# bqZUM_USB.net
KiCad netlist of a schematic drawn in Altium Designer
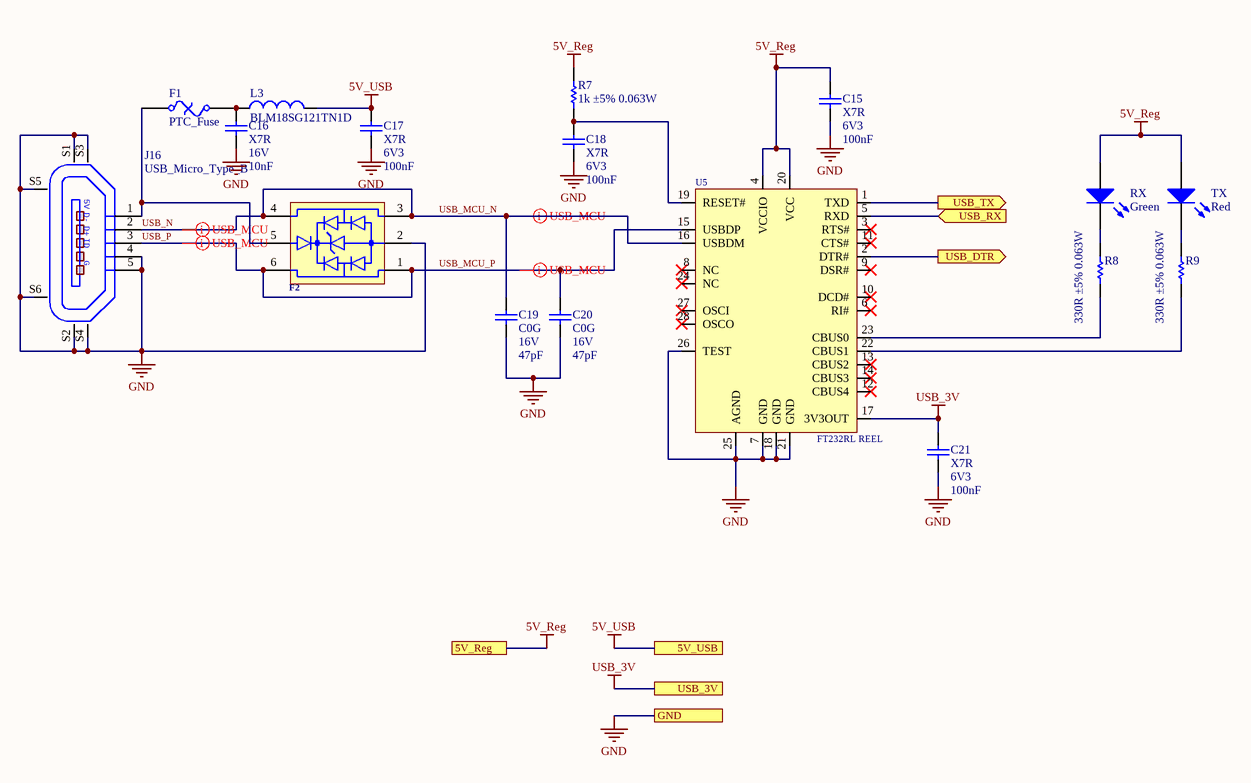
[diagram p0: bqZUM_USB.SchDoc]

(export (version "E")
  (design (tool "Eeschema 10.0.6"))
  (components
    (comp (ref "C15")
      (value "Capacitor")
      (footprint "C0402")
      (fields
        (field (name "DIELECTRIC") "X7R")
        (field (name "VOLTAGE") "6V3")
        (field (name "CAPACITANCE") "100nF")
        (field (name "PART NUMBER") "C0402_100nF_6V3_±10%")
        (field (name "TOLERANCE") "±10%")
        (field (name "MANUFACTURER") "Kemet")
      )
      (libsource (lib "Pasives_Capacitor_SMD") (part "Capacitor"))
    )
    (comp (ref "C16")
      (value "Capacitor")
      (footprint "C0402")
      (fields
        (field (name "DIELECTRIC") "X7R")
        (field (name "VOLTAGE") "16V")
        (field (name "CAPACITANCE") "10nF")
        (field (name "PART NUMBER") "C0402_10nF_16V_±10%")
        (field (name "TOLERANCE") "±10%")
        (field (name "MANUFACTURER") "Kemet")
      )
      (libsource (lib "Pasives_Capacitor_SMD") (part "Capacitor"))
    )
    (comp (ref "C17")
      (value "Capacitor")
      (footprint "C0402")
      (fields
        (field (name "DIELECTRIC") "X7R")
        (field (name "VOLTAGE") "6V3")
        (field (name "CAPACITANCE") "100nF")
        (field (name "PART NUMBER") "C0402_100nF_6V3_±10%")
        (field (name "TOLERANCE") "±10%")
        (field (name "MANUFACTURER") "Kemet")
      )
      (libsource (lib "Pasives_Capacitor_SMD") (part "Capacitor"))
    )
    (comp (ref "C18")
      (value "Capacitor")
      (footprint "C0402")
      (fields
        (field (name "DIELECTRIC") "X7R")
        (field (name "VOLTAGE") "6V3")
        (field (name "CAPACITANCE") "100nF")
        (field (name "PART NUMBER") "C0402_100nF_6V3_±10%")
        (field (name "TOLERANCE") "±10%")
        (field (name "MANUFACTURER") "Kemet")
      )
      (libsource (lib "Pasives_Capacitor_SMD") (part "Capacitor"))
    )
    (comp (ref "C19")
      (value "Capacitor")
      (footprint "C0402")
      (fields
        (field (name "DIELECTRIC") "C0G")
        (field (name "VOLTAGE") "16V")
        (field (name "CAPACITANCE") "47pF")
        (field (name "PART NUMBER") "C0402_47pF_16V_±10%")
        (field (name "TOLERANCE") "±10%")
        (field (name "MANUFACTURER") "Kemet")
      )
      (libsource (lib "Pasives_Capacitor_SMD") (part "Capacitor"))
    )
    (comp (ref "C20")
      (value "Capacitor")
      (footprint "C0402")
      (fields
        (field (name "DIELECTRIC") "C0G")
        (field (name "VOLTAGE") "16V")
        (field (name "CAPACITANCE") "47pF")
        (field (name "PART NUMBER") "C0402_47pF_16V_±10%")
        (field (name "TOLERANCE") "±10%")
        (field (name "MANUFACTURER") "Kemet")
      )
      (libsource (lib "Pasives_Capacitor_SMD") (part "Capacitor"))
    )
    (comp (ref "C21")
      (value "Capacitor")
      (footprint "C0402")
      (fields
        (field (name "DIELECTRIC") "X7R")
        (field (name "VOLTAGE") "6V3")
        (field (name "CAPACITANCE") "100nF")
        (field (name "PART NUMBER") "C0402_100nF_6V3_±10%")
        (field (name "TOLERANCE") "±10%")
        (field (name "MANUFACTURER") "Kemet")
      )
      (libsource (lib "Pasives_Capacitor_SMD") (part "Capacitor"))
    )
    (comp (ref "F1")
      (value "PTC_Fuse")
      (footprint "F1812")
      (description "PTC Resettable Fuse")
      (fields (field (name "PART NUMBER") "FUSE 0.5A 15V") (field (name "VOLTAGE") "15V"))
      (libsource (lib "Protection") (part "PTC_Fuse"))
    )
    (comp (ref "F2")
      (value "ESDUSB")
      (footprint "SOT563")
      (description "USB ESD Protection")
      (fields (field (name "PART NUMBER") "USB ESD Single") (field (name "MANUFACTURER") "Würth"))
      (libsource (lib "Protection") (part "ESDUSB"))
    )
    (comp (ref "J16")
      (value "USB_Micro_Type_B")
      (footprint "USB_Micro_B")
      (description "USB Micro B")
      (fields
        (field (name "PART NUMBER") "Micro USB Type B SMD")
        (field (name "MANUFACTURER") "Hirose Connector")
      )
      (libsource (lib "Connectors_USB") (part "USB_Micro_Type_B"))
    )
    (comp (ref "L3")
      (value "BLM18SG121TN1D")
      (footprint "L0603")
      (fields (field (name "PART NUMBER") "L0603_120R_0,025R_3000mA") (field (name "MANUFACTURER") "Murata"))
      (libsource (lib "Pasivos_Inductor_SMD") (part "Ferrite Bead"))
    )
    (comp (ref "R7")
      (value "1k ±5% 0.063W")
      (footprint "R0402")
      (description "Resistor")
      (fields (field (name "TOLERANCE") "±5%") (field (name "POWER") "0.063W"))
      (libsource (lib "Pasives_Resistor_SMD") (part "Resistor"))
    )
    (comp (ref "R8")
      (value "330R ±5% 0.063W")
      (footprint "R0402")
      (description "Resistor")
      (fields (field (name "TOLERANCE") "±5%") (field (name "POWER") "0.063W"))
      (libsource (lib "Pasives_Resistor_SMD") (part "Resistor"))
    )
    (comp (ref "R9")
      (value "330R ±5% 0.063W")
      (footprint "R0402")
      (description "Resistor")
      (fields (field (name "TOLERANCE") "±5%") (field (name "POWER") "0.063W"))
      (libsource (lib "Pasives_Resistor_SMD") (part "Resistor"))
    )
    (comp (ref "RX")
      (value "Green")
      (footprint "LED0603")
      (description "Light Emitting Diode")
      (fields (field (name "PART NUMBER") "HSMG-C190") (field (name "MANUFACTURER") "Avago Technologies"))
      (libsource (lib "Optoelectronics") (part "LED"))
    )
    (comp (ref "TX")
      (value "Red")
      (footprint "LED0603")
      (description "Light Emitting Diode")
      (fields (field (name "PART NUMBER") "HSMH-C190") (field (name "MANUFACTURER") "Avago Technologies"))
      (libsource (lib "Optoelectronics") (part "LED"))
    )
    (comp (ref "U5")
      (value "FT232RL REEL")
      (footprint "SSOP28")
      (description "IC USB TO SERIAL UART 28-SSOP")
      (fields (field (name "PART NUMBER") "FT232RL") (field (name "MANUFACTURER") "FTDI"))
      (libsource (lib "Transceiver") (part "FT232RL"))
    )
  )
  (nets
    (net (code "1") (name "/USB_DTR") (class "Default")
      (node (ref "U5") (pin "2") (pinfunction "DTR#_2") (pintype "passive"))
    )
    (net (code "2") (name "/USB_MCU_N") (class "Default")
      (node (ref "C19") (pin "2") (pinfunction "2_2") (pintype "passive"))
      (node (ref "F2") (pin "3") (pinfunction "3_3") (pintype "passive"))
      (node (ref "F2") (pin "4") (pinfunction "4_4") (pintype "passive"))
      (node (ref "J16") (pin "2") (pinfunction "P2_2") (pintype "passive"))
      (node (ref "U5") (pin "16") (pinfunction "USBDM_16") (pintype "passive"))
    )
    (net (code "3") (name "/USB_MCU_P") (class "Default")
      (node (ref "C20") (pin "2") (pinfunction "2_2") (pintype "passive"))
      (node (ref "F2") (pin "1") (pinfunction "1_1") (pintype "passive"))
      (node (ref "F2") (pin "6") (pinfunction "6_6") (pintype "passive"))
      (node (ref "J16") (pin "3") (pinfunction "P3_3") (pintype "passive"))
      (node (ref "U5") (pin "15") (pinfunction "USBDP_15") (pintype "passive"))
    )
    (net (code "4") (name "/USB_RX") (class "Default")
      (node (ref "U5") (pin "5") (pinfunction "RXD_5") (pintype "passive"))
    )
    (net (code "5") (name "/USB_TX") (class "Default")
      (node (ref "U5") (pin "1") (pinfunction "TXD_1") (pintype "passive"))
    )
    (net (code "6") (name "5V_Reg") (class "Default")
      (node (ref "C15") (pin "2") (pinfunction "2_2") (pintype "passive"))
      (node (ref "R7") (pin "2") (pinfunction "2_2") (pintype "passive"))
      (node (ref "RX") (pin "A") (pinfunction "A_A") (pintype "passive"))
      (node (ref "TX") (pin "A") (pinfunction "A_A") (pintype "passive"))
      (node (ref "U5") (pin "20") (pinfunction "VCC_20") (pintype "passive"))
      (node (ref "U5") (pin "4") (pinfunction "VCCIO_4") (pintype "passive"))
    )
    (net (code "7") (name "5V_USB") (class "Default")
      (node (ref "C17") (pin "2") (pinfunction "2_2") (pintype "passive"))
      (node (ref "L3") (pin "2") (pinfunction "2_2") (pintype "passive"))
    )
    (net (code "8") (name "GND") (class "Default")
      (node (ref "C15") (pin "1") (pinfunction "1_1") (pintype "passive"))
      (node (ref "C16") (pin "1") (pinfunction "1_1") (pintype "passive"))
      (node (ref "C17") (pin "1") (pinfunction "1_1") (pintype "passive"))
      (node (ref "C18") (pin "1") (pinfunction "1_1") (pintype "passive"))
      (node (ref "C19") (pin "1") (pinfunction "1_1") (pintype "passive"))
      (node (ref "C20") (pin "1") (pinfunction "1_1") (pintype "passive"))
      (node (ref "C21") (pin "2") (pinfunction "2_2") (pintype "passive"))
      (node (ref "F2") (pin "2") (pinfunction "2_2") (pintype "passive"))
      (node (ref "J16") (pin "4") (pinfunction "P4_4") (pintype "passive"))
      (node (ref "J16") (pin "5") (pinfunction "P5_5") (pintype "passive"))
      (node (ref "J16") (pin "S1") (pinfunction "SHLD1_S1") (pintype "passive"))
      (node (ref "J16") (pin "S2") (pinfunction "SHLD2_S2") (pintype "passive"))
      (node (ref "J16") (pin "S3") (pinfunction "SHLD3_S3") (pintype "passive"))
      (node (ref "J16") (pin "S4") (pinfunction "SHLD4_S4") (pintype "passive"))
      (node (ref "J16") (pin "S5") (pinfunction "SHLD5_S5") (pintype "passive"))
      (node (ref "J16") (pin "S6") (pinfunction "SHLD6_S6") (pintype "passive"))
      (node (ref "U5") (pin "18") (pinfunction "GND_18") (pintype "passive"))
      (node (ref "U5") (pin "21") (pinfunction "GND_21") (pintype "passive"))
      (node (ref "U5") (pin "25") (pinfunction "AGND_25") (pintype "passive"))
      (node (ref "U5") (pin "26") (pinfunction "TEST_26") (pintype "passive"))
      (node (ref "U5") (pin "7") (pinfunction "GND_7") (pintype "passive"))
    )
    (net (code "9") (name "Net-(C16-Pad2)") (class "Default")
      (node (ref "C16") (pin "2") (pinfunction "2_2") (pintype "passive"))
      (node (ref "F1") (pin "2") (pinfunction "2_2") (pintype "passive"))
      (node (ref "L3") (pin "1") (pinfunction "1_1") (pintype "passive"))
    )
    (net (code "10") (name "Net-(J16-P1)") (class "Default")
      (node (ref "F1") (pin "1") (pinfunction "1_1") (pintype "passive"))
      (node (ref "F2") (pin "5") (pinfunction "5_5") (pintype "passive"))
      (node (ref "J16") (pin "1") (pinfunction "P1_1") (pintype "passive"))
    )
    (net (code "11") (name "Net-(R8-Pad2)") (class "Default")
      (node (ref "R8") (pin "2") (pinfunction "2_2") (pintype "passive"))
      (node (ref "RX") (pin "K") (pinfunction "K_K") (pintype "passive"))
    )
    (net (code "12") (name "Net-(R9-Pad2)") (class "Default")
      (node (ref "R9") (pin "2") (pinfunction "2_2") (pintype "passive"))
      (node (ref "TX") (pin "K") (pinfunction "K_K") (pintype "passive"))
    )
    (net (code "13") (name "Net-(U5-CBUS0)") (class "Default")
      (node (ref "R8") (pin "1") (pinfunction "1_1") (pintype "passive"))
      (node (ref "U5") (pin "23") (pinfunction "CBUS0_23") (pintype "passive"))
    )
    (net (code "14") (name "Net-(U5-CBUS1)") (class "Default")
      (node (ref "R9") (pin "1") (pinfunction "1_1") (pintype "passive"))
      (node (ref "U5") (pin "22") (pinfunction "CBUS1_22") (pintype "passive"))
    )
    (net (code "15") (name "Net-(U5-RESET#)") (class "Default")
      (node (ref "C18") (pin "2") (pinfunction "2_2") (pintype "passive"))
      (node (ref "R7") (pin "1") (pinfunction "1_1") (pintype "passive"))
      (node (ref "U5") (pin "19") (pinfunction "RESET#_19") (pintype "passive"))
    )
    (net (code "16") (name "USB_3V") (class "Default")
      (node (ref "C21") (pin "1") (pinfunction "1_1") (pintype "passive"))
      (node (ref "U5") (pin "17") (pinfunction "3V3OUT_17") (pintype "passive"))
    )
    (net (code "17") (name "unconnected-(U5-CBUS2-Pad13)") (class "Default")
      (node (ref "U5") (pin "13") (pinfunction "CBUS2_13") (pintype "passive+no_connect"))
    )
    (net (code "18") (name "unconnected-(U5-CBUS3-Pad14)") (class "Default")
      (node (ref "U5") (pin "14") (pinfunction "CBUS3_14") (pintype "passive+no_connect"))
    )
    (net (code "19") (name "unconnected-(U5-CBUS4-Pad12)") (class "Default")
      (node (ref "U5") (pin "12") (pinfunction "CBUS4_12") (pintype "passive+no_connect"))
    )
    (net (code "20") (name "unconnected-(U5-CTS#-Pad11)") (class "Default")
      (node (ref "U5") (pin "11") (pinfunction "CTS#_11") (pintype "passive+no_connect"))
    )
    (net (code "21") (name "unconnected-(U5-DCD#-Pad10)") (class "Default")
      (node (ref "U5") (pin "10") (pinfunction "DCD#_10") (pintype "passive+no_connect"))
    )
    (net (code "22") (name "unconnected-(U5-DSR#-Pad9)") (class "Default")
      (node (ref "U5") (pin "9") (pinfunction "DSR#_9") (pintype "passive+no_connect"))
    )
    (net (code "23") (name "unconnected-(U5-NC-Pad8)") (class "Default")
      (node (ref "U5") (pin "8") (pinfunction "NC_8") (pintype "passive+no_connect"))
    )
    (net (code "24") (name "unconnected-(U5-NC-Pad24)") (class "Default")
      (node (ref "U5") (pin "24") (pinfunction "NC_24") (pintype "passive+no_connect"))
    )
    (net (code "25") (name "unconnected-(U5-OSCI-Pad27)") (class "Default")
      (node (ref "U5") (pin "27") (pinfunction "OSCI_27") (pintype "passive+no_connect"))
    )
    (net (code "26") (name "unconnected-(U5-OSCO-Pad28)") (class "Default")
      (node (ref "U5") (pin "28") (pinfunction "OSCO_28") (pintype "passive+no_connect"))
    )
    (net (code "27") (name "unconnected-(U5-RI#-Pad6)") (class "Default")
      (node (ref "U5") (pin "6") (pinfunction "RI#_6") (pintype "passive+no_connect"))
    )
    (net (code "28") (name "unconnected-(U5-RTS#-Pad3)") (class "Default")
      (node (ref "U5") (pin "3") (pinfunction "RTS#_3") (pintype "passive+no_connect"))
    )
  )
)
